# predkosciomierz.net
KiCad netlist of a schematic drawn in EAGLE
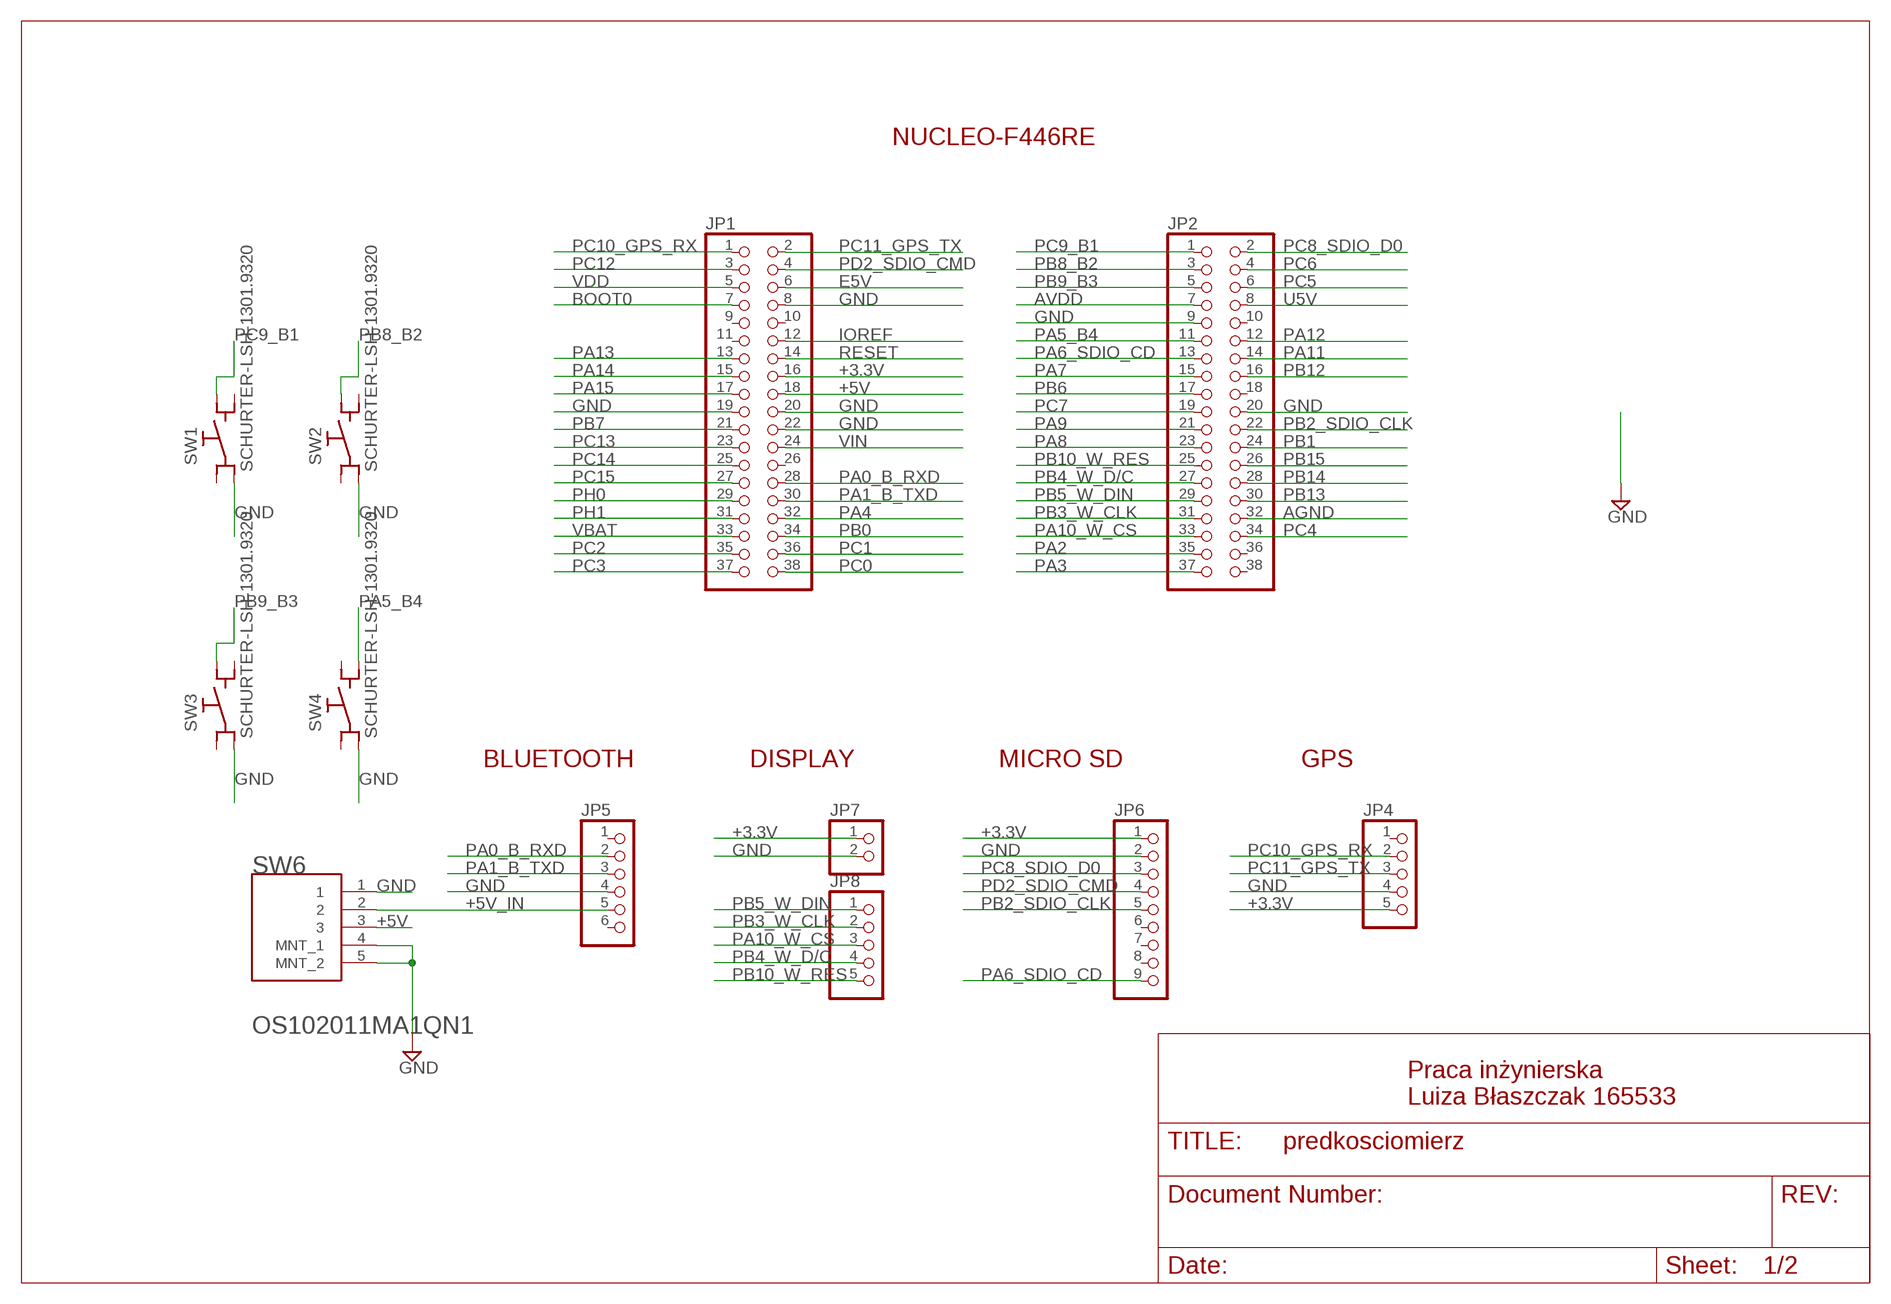
[diagram p0: schematic, sheet 1]
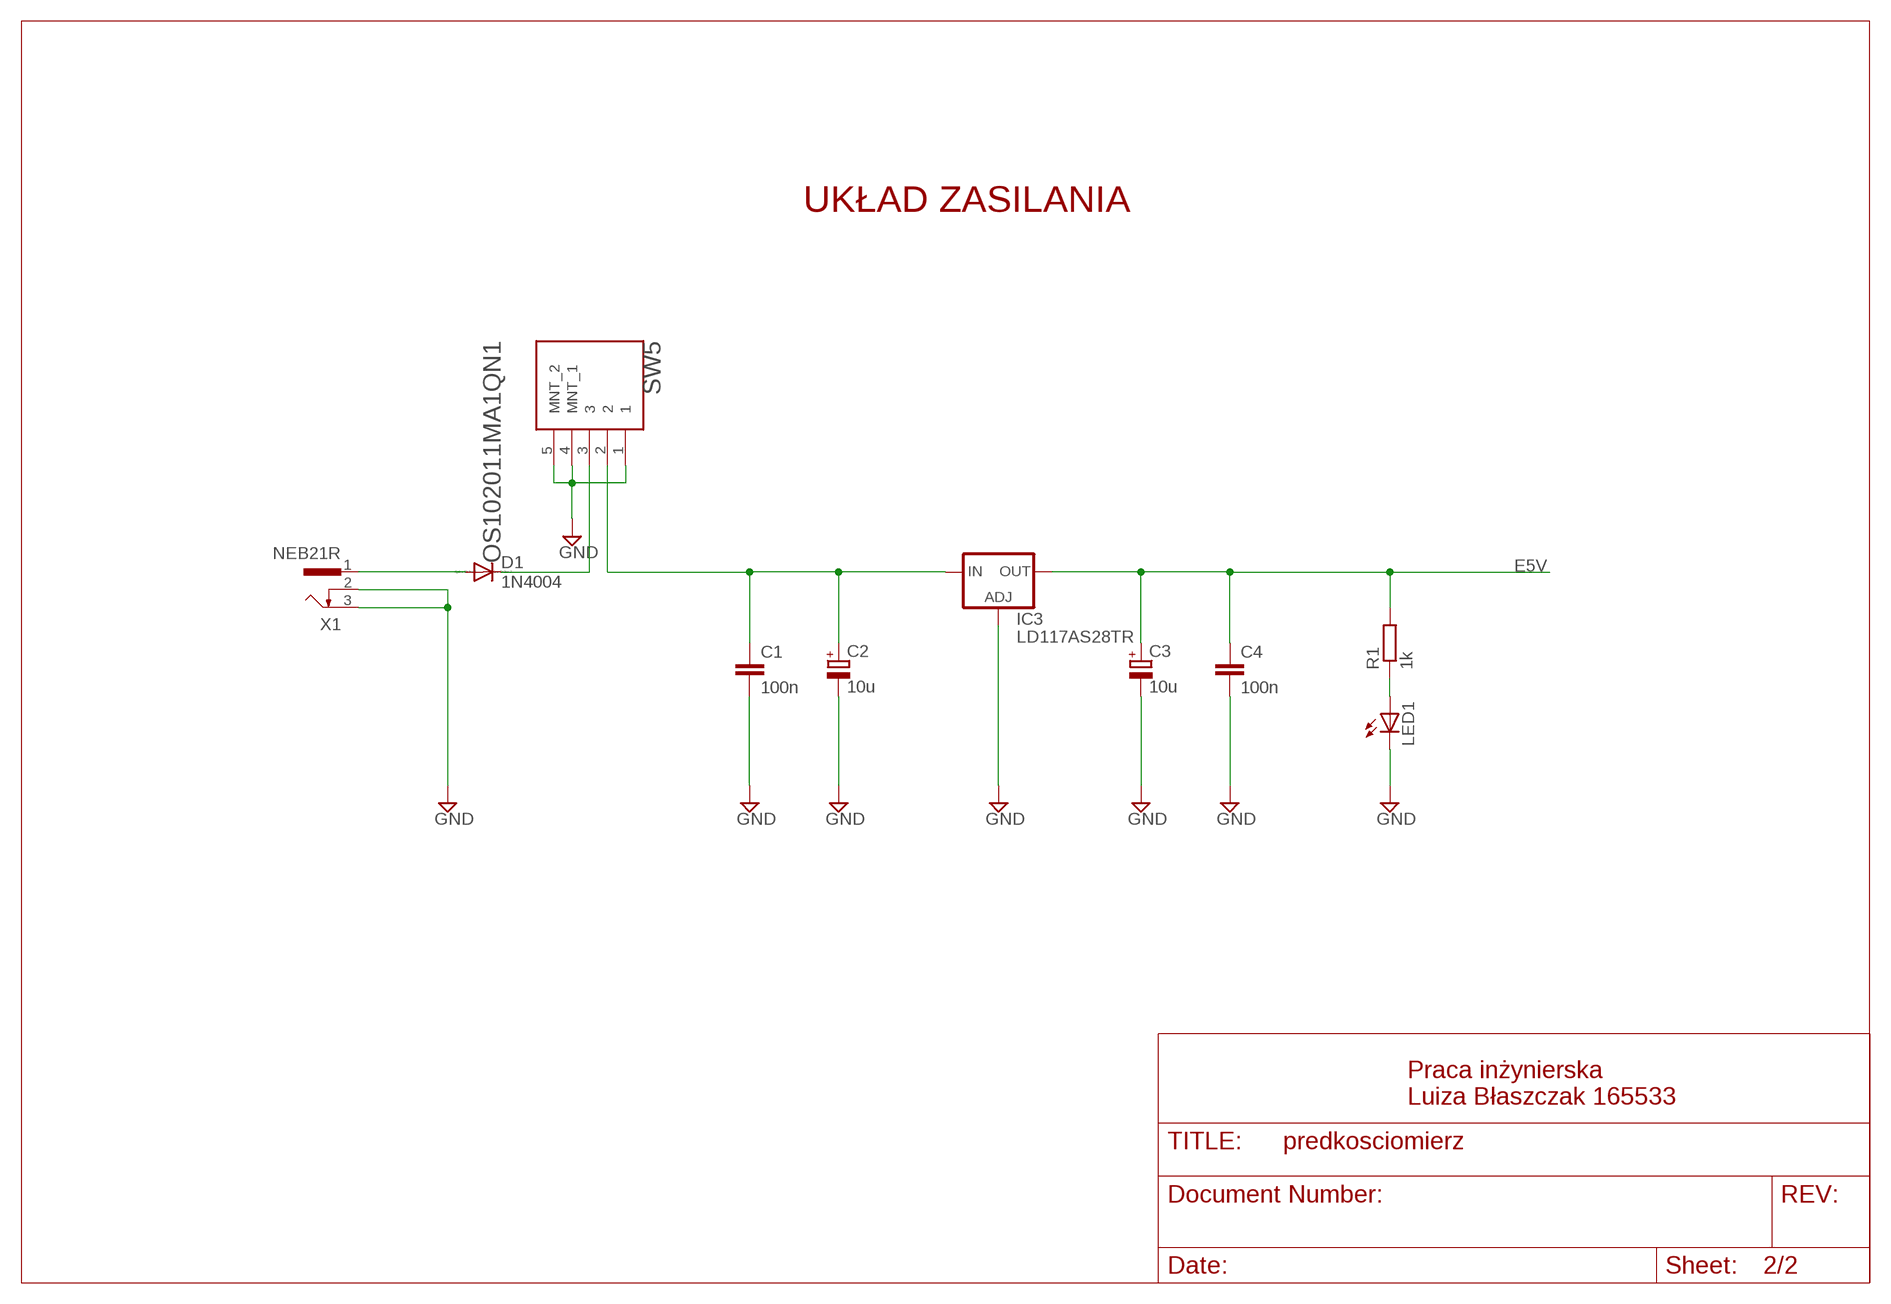
[diagram p1: schematic, sheet 2]

(export (version "E")
  (design (tool "Eeschema 10.0.6"))
  (components
    (comp (ref "JP1")
      (value "PINHD-2X19")
      (footprint "eagle-import:2X19")
      (libsource (lib "eagle-import") (part "PINHD-2X19"))
    )
    (comp (ref "JP2")
      (value "PINHD-2X19")
      (footprint "eagle-import:2X19")
      (libsource (lib "eagle-import") (part "PINHD-2X19"))
    )
    (comp (ref "JP4")
      (value "PINHD-1X5")
      (footprint "eagle-import:1X05")
      (libsource (lib "eagle-import") (part "PINHD-1X5"))
    )
    (comp (ref "JP5")
      (value "PINHD-1X6")
      (footprint "eagle-import:1X06")
      (libsource (lib "eagle-import") (part "PINHD-1X6"))
    )
    (comp (ref "JP6")
      (value "PINHD-1X9")
      (footprint "eagle-import:1X09")
      (libsource (lib "eagle-import") (part "PINHD-1X9"))
    )
    (comp (ref "JP7")
      (value "PINHD-1X2")
      (footprint "eagle-import:1X02")
      (libsource (lib "eagle-import") (part "PINHD-1X2"))
    )
    (comp (ref "JP8")
      (value "PINHD-1X5")
      (footprint "eagle-import:1X05")
      (libsource (lib "eagle-import") (part "PINHD-1X5"))
    )
    (comp (ref "SW1")
      (value "SCHURTER-LSH-1301.9320")
      (footprint "eagle-import:LSH")
      (libsource (lib "eagle-import") (part "SCHURTER-LSH-1301.9320"))
    )
    (comp (ref "SW2")
      (value "SCHURTER-LSH-1301.9320")
      (footprint "eagle-import:LSH")
      (libsource (lib "eagle-import") (part "SCHURTER-LSH-1301.9320"))
    )
    (comp (ref "SW3")
      (value "SCHURTER-LSH-1301.9320")
      (footprint "eagle-import:LSH")
      (libsource (lib "eagle-import") (part "SCHURTER-LSH-1301.9320"))
    )
    (comp (ref "SW4")
      (value "SCHURTER-LSH-1301.9320")
      (footprint "eagle-import:LSH")
      (libsource (lib "eagle-import") (part "SCHURTER-LSH-1301.9320"))
    )
    (comp (ref "SW6")
      (value "C&K_OS102011MA1QN1C&K_OS102011MA1QN1_0_0")
      (footprint "eagle-import:C&K_OS102011MA1QN1_0")
      (fields
        (field (name "DIGIKEY_PART_NUMBER") "CKN9559-ND")
        (field (name "MF") "C&K")
        (field (name "MOUSER_PART_NUMBER") "OS102011MA1QN1")
      )
      (libsource (lib "eagle-import") (part "C&K_OS102011MA1QN1C&K_OS102011MA1QN1_0_0"))
    )
    (comp (ref "C1")
      (value "100n")
      (footprint "eagle-import:C1210")
      (libsource (lib "eagle-import") (part "C-EUC1210"))
    )
    (comp (ref "C2")
      (value "10u")
      (footprint "eagle-import:E2-5")
      (libsource (lib "eagle-import") (part "CPOL-EUE2-5"))
    )
    (comp (ref "C3")
      (value "10u")
      (footprint "eagle-import:E2-5")
      (libsource (lib "eagle-import") (part "CPOL-EUE2-5"))
    )
    (comp (ref "C4")
      (value "100n")
      (footprint "eagle-import:C1210")
      (libsource (lib "eagle-import") (part "C-EUC1210"))
    )
    (comp (ref "D1")
      (value "1N4004")
      (footprint "eagle-import:DO41-10")
      (libsource (lib "eagle-import") (part "1N4004"))
    )
    (comp (ref "IC3")
      (value "LD117AS28TR")
      (footprint "eagle-import:SOT223")
      (libsource (lib "eagle-import") (part "LD117A?S28TR"))
    )
    (comp (ref "LED1")
      (value "LED5MM")
      (footprint "eagle-import:LED5MM")
      (libsource (lib "eagle-import") (part "LED5MM"))
    )
    (comp (ref "R1")
      (value "1k")
      (footprint "eagle-import:0204_7")
      (libsource (lib "eagle-import") (part "R-EU_0204/7"))
    )
    (comp (ref "SW5")
      (value "C&K_OS102011MA1QN1C&K_OS102011MA1QN1_0_0")
      (footprint "eagle-import:C&K_OS102011MA1QN1_0")
      (fields
        (field (name "DIGIKEY_PART_NUMBER") "CKN9559-ND")
        (field (name "MF") "C&K")
        (field (name "MOUSER_PART_NUMBER") "OS102011MA1QN1")
      )
      (libsource (lib "eagle-import") (part "C&K_OS102011MA1QN1C&K_OS102011MA1QN1_0_0"))
    )
    (comp (ref "X1")
      (value "NEB21R")
      (footprint "eagle-import:NEB21R")
      (fields (field (name "MPN") "NEB 21 R"))
      (libsource (lib "eagle-import") (part "NEB21R"))
    )
  )
  (nets
    (net (code "1") (name "+3.3V") (class "Default")
      (node (ref "JP1") (pin "16") (pinfunction "16_16") (pintype "passive"))
      (node (ref "JP4") (pin "5") (pinfunction "5_5") (pintype "passive"))
      (node (ref "JP6") (pin "1") (pinfunction "1_1") (pintype "passive"))
      (node (ref "JP7") (pin "1") (pinfunction "1_1") (pintype "passive"))
    )
    (net (code "2") (name "+5V") (class "Default")
      (node (ref "JP1") (pin "18") (pinfunction "18_18") (pintype "passive"))
      (node (ref "SW6") (pin "3") (pinfunction "3_3") (pintype "passive"))
    )
    (net (code "3") (name "+5V_IN") (class "Default")
      (node (ref "JP5") (pin "5") (pinfunction "5_5") (pintype "passive"))
      (node (ref "SW6") (pin "2") (pinfunction "2_2") (pintype "passive"))
    )
    (net (code "4") (name "AGND") (class "Default")
      (node (ref "JP2") (pin "32") (pinfunction "32_32") (pintype "passive"))
    )
    (net (code "5") (name "AVDD") (class "Default")
      (node (ref "JP2") (pin "7") (pinfunction "7_7") (pintype "passive"))
    )
    (net (code "6") (name "BOOT0") (class "Default")
      (node (ref "JP1") (pin "7") (pinfunction "7_7") (pintype "passive"))
    )
    (net (code "7") (name "E5V") (class "Default")
      (node (ref "C3") (pin "+") (pinfunction "+_+") (pintype "passive"))
      (node (ref "C4") (pin "1") (pinfunction "1_1") (pintype "passive"))
      (node (ref "IC3") (pin "4") (pinfunction "OUT_4") (pintype "passive"))
      (node (ref "JP1") (pin "6") (pinfunction "6_6") (pintype "passive"))
      (node (ref "R1") (pin "2") (pinfunction "2_2") (pintype "passive"))
    )
    (net (code "8") (name "GND") (class "Default")
      (node (ref "C1") (pin "2") (pinfunction "2_2") (pintype "passive"))
      (node (ref "C2") (pin "-") (pinfunction "-_-") (pintype "passive"))
      (node (ref "C3") (pin "-") (pinfunction "-_-") (pintype "passive"))
      (node (ref "C4") (pin "2") (pinfunction "2_2") (pintype "passive"))
      (node (ref "IC3") (pin "1") (pinfunction "ADJ_1") (pintype "input"))
      (node (ref "JP1") (pin "19") (pinfunction "19_19") (pintype "passive"))
      (node (ref "JP1") (pin "20") (pinfunction "20_20") (pintype "passive"))
      (node (ref "JP1") (pin "22") (pinfunction "22_22") (pintype "passive"))
      (node (ref "JP1") (pin "8") (pinfunction "8_8") (pintype "passive"))
      (node (ref "JP2") (pin "20") (pinfunction "20_20") (pintype "passive"))
      (node (ref "JP2") (pin "9") (pinfunction "9_9") (pintype "passive"))
      (node (ref "JP4") (pin "4") (pinfunction "4_4") (pintype "passive"))
      (node (ref "JP5") (pin "4") (pinfunction "4_4") (pintype "passive"))
      (node (ref "JP6") (pin "2") (pinfunction "2_2") (pintype "passive"))
      (node (ref "JP7") (pin "2") (pinfunction "2_2") (pintype "passive"))
      (node (ref "LED1") (pin "K") (pinfunction "C_K") (pintype "passive"))
      (node (ref "SW1") (pin "C2") (pinfunction "C_C2") (pintype "passive"))
      (node (ref "SW2") (pin "C2") (pinfunction "C_C2") (pintype "passive"))
      (node (ref "SW3") (pin "C2") (pinfunction "C_C2") (pintype "passive"))
      (node (ref "SW4") (pin "C2") (pinfunction "C_C2") (pintype "passive"))
      (node (ref "SW5") (pin "1") (pinfunction "1_1") (pintype "passive"))
      (node (ref "SW5") (pin "4") (pinfunction "MNT_1_4") (pintype "passive"))
      (node (ref "SW5") (pin "5") (pinfunction "MNT_2_5") (pintype "passive"))
      (node (ref "SW6") (pin "1") (pinfunction "1_1") (pintype "passive"))
      (node (ref "SW6") (pin "4") (pinfunction "MNT_1_4") (pintype "passive"))
      (node (ref "SW6") (pin "5") (pinfunction "MNT_2_5") (pintype "passive"))
      (node (ref "X1") (pin "2") (pinfunction "2_2") (pintype "passive"))
      (node (ref "X1") (pin "3") (pinfunction "3_3") (pintype "passive"))
    )
    (net (code "9") (name "IOREF") (class "Default")
      (node (ref "JP1") (pin "12") (pinfunction "12_12") (pintype "passive"))
    )
    (net (code "10") (name "Net-(D1-PadA)") (class "Default")
      (node (ref "D1") (pin "A") (pinfunction "A_A") (pintype "passive"))
      (node (ref "X1") (pin "1") (pinfunction "1_1") (pintype "passive"))
    )
    (net (code "11") (name "Net-(D1-PadC)") (class "Default")
      (node (ref "D1") (pin "C") (pinfunction "C_C") (pintype "passive"))
      (node (ref "SW5") (pin "3") (pinfunction "3_3") (pintype "passive"))
    )
    (net (code "12") (name "Net-(IC3-IN)") (class "Default")
      (node (ref "C1") (pin "1") (pinfunction "1_1") (pintype "passive"))
      (node (ref "C2") (pin "+") (pinfunction "+_+") (pintype "passive"))
      (node (ref "IC3") (pin "3") (pinfunction "IN_3") (pintype "input"))
      (node (ref "SW5") (pin "2") (pinfunction "2_2") (pintype "passive"))
    )
    (net (code "13") (name "Net-(LED1-PadA)") (class "Default")
      (node (ref "LED1") (pin "A") (pinfunction "A_A") (pintype "passive"))
      (node (ref "R1") (pin "1") (pinfunction "1_1") (pintype "passive"))
    )
    (net (code "14") (name "PA0_B_RXD") (class "Default")
      (node (ref "JP1") (pin "28") (pinfunction "28_28") (pintype "passive"))
      (node (ref "JP5") (pin "2") (pinfunction "2_2") (pintype "passive"))
    )
    (net (code "15") (name "PA1_B_TXD") (class "Default")
      (node (ref "JP1") (pin "30") (pinfunction "30_30") (pintype "passive"))
      (node (ref "JP5") (pin "3") (pinfunction "3_3") (pintype "passive"))
    )
    (net (code "16") (name "PA2") (class "Default")
      (node (ref "JP2") (pin "35") (pinfunction "35_35") (pintype "passive"))
    )
    (net (code "17") (name "PA3") (class "Default")
      (node (ref "JP2") (pin "37") (pinfunction "37_37") (pintype "passive"))
    )
    (net (code "18") (name "PA4") (class "Default")
      (node (ref "JP1") (pin "32") (pinfunction "32_32") (pintype "passive"))
    )
    (net (code "19") (name "PA5_B4") (class "Default")
      (node (ref "JP2") (pin "11") (pinfunction "11_11") (pintype "passive"))
      (node (ref "SW4") (pin "NO2") (pinfunction "NO_NO2") (pintype "passive"))
    )
    (net (code "20") (name "PA6_SDIO_CD") (class "Default")
      (node (ref "JP2") (pin "13") (pinfunction "13_13") (pintype "passive"))
      (node (ref "JP6") (pin "9") (pinfunction "9_9") (pintype "passive"))
    )
    (net (code "21") (name "PA7") (class "Default")
      (node (ref "JP2") (pin "15") (pinfunction "15_15") (pintype "passive"))
    )
    (net (code "22") (name "PA8") (class "Default")
      (node (ref "JP2") (pin "23") (pinfunction "23_23") (pintype "passive"))
    )
    (net (code "23") (name "PA9") (class "Default")
      (node (ref "JP2") (pin "21") (pinfunction "21_21") (pintype "passive"))
    )
    (net (code "24") (name "PA10_W_CS") (class "Default")
      (node (ref "JP2") (pin "33") (pinfunction "33_33") (pintype "passive"))
      (node (ref "JP8") (pin "3") (pinfunction "3_3") (pintype "passive"))
    )
    (net (code "25") (name "PA11") (class "Default")
      (node (ref "JP2") (pin "14") (pinfunction "14_14") (pintype "passive"))
    )
    (net (code "26") (name "PA12") (class "Default")
      (node (ref "JP2") (pin "12") (pinfunction "12_12") (pintype "passive"))
    )
    (net (code "27") (name "PA13") (class "Default")
      (node (ref "JP1") (pin "13") (pinfunction "13_13") (pintype "passive"))
    )
    (net (code "28") (name "PA14") (class "Default")
      (node (ref "JP1") (pin "15") (pinfunction "15_15") (pintype "passive"))
    )
    (net (code "29") (name "PA15") (class "Default")
      (node (ref "JP1") (pin "17") (pinfunction "17_17") (pintype "passive"))
    )
    (net (code "30") (name "PB0") (class "Default")
      (node (ref "JP1") (pin "34") (pinfunction "34_34") (pintype "passive"))
    )
    (net (code "31") (name "PB1") (class "Default")
      (node (ref "JP2") (pin "24") (pinfunction "24_24") (pintype "passive"))
    )
    (net (code "32") (name "PB2_SDIO_CLK") (class "Default")
      (node (ref "JP2") (pin "22") (pinfunction "22_22") (pintype "passive"))
      (node (ref "JP6") (pin "5") (pinfunction "5_5") (pintype "passive"))
    )
    (net (code "33") (name "PB3_W_CLK") (class "Default")
      (node (ref "JP2") (pin "31") (pinfunction "31_31") (pintype "passive"))
      (node (ref "JP8") (pin "2") (pinfunction "2_2") (pintype "passive"))
    )
    (net (code "34") (name "PB4_W_D{slash}C") (class "Default")
      (node (ref "JP2") (pin "27") (pinfunction "27_27") (pintype "passive"))
      (node (ref "JP8") (pin "4") (pinfunction "4_4") (pintype "passive"))
    )
    (net (code "35") (name "PB5_W_DIN") (class "Default")
      (node (ref "JP2") (pin "29") (pinfunction "29_29") (pintype "passive"))
      (node (ref "JP8") (pin "1") (pinfunction "1_1") (pintype "passive"))
    )
    (net (code "36") (name "PB6") (class "Default")
      (node (ref "JP2") (pin "17") (pinfunction "17_17") (pintype "passive"))
    )
    (net (code "37") (name "PB7") (class "Default")
      (node (ref "JP1") (pin "21") (pinfunction "21_21") (pintype "passive"))
    )
    (net (code "38") (name "PB8_B2") (class "Default")
      (node (ref "JP2") (pin "3") (pinfunction "3_3") (pintype "passive"))
      (node (ref "SW2") (pin "NO1") (pinfunction "NO_NO1") (pintype "passive"))
    )
    (net (code "39") (name "PB9_B3") (class "Default")
      (node (ref "JP2") (pin "5") (pinfunction "5_5") (pintype "passive"))
      (node (ref "SW3") (pin "NO1") (pinfunction "NO_NO1") (pintype "passive"))
    )
    (net (code "40") (name "PB10_W_RES") (class "Default")
      (node (ref "JP2") (pin "25") (pinfunction "25_25") (pintype "passive"))
      (node (ref "JP8") (pin "5") (pinfunction "5_5") (pintype "passive"))
    )
    (net (code "41") (name "PB12") (class "Default")
      (node (ref "JP2") (pin "16") (pinfunction "16_16") (pintype "passive"))
    )
    (net (code "42") (name "PB13") (class "Default")
      (node (ref "JP2") (pin "30") (pinfunction "30_30") (pintype "passive"))
    )
    (net (code "43") (name "PB14") (class "Default")
      (node (ref "JP2") (pin "28") (pinfunction "28_28") (pintype "passive"))
    )
    (net (code "44") (name "PB15") (class "Default")
      (node (ref "JP2") (pin "26") (pinfunction "26_26") (pintype "passive"))
    )
    (net (code "45") (name "PC0") (class "Default")
      (node (ref "JP1") (pin "38") (pinfunction "38_38") (pintype "passive"))
    )
    (net (code "46") (name "PC1") (class "Default")
      (node (ref "JP1") (pin "36") (pinfunction "36_36") (pintype "passive"))
    )
    (net (code "47") (name "PC2") (class "Default")
      (node (ref "JP1") (pin "35") (pinfunction "35_35") (pintype "passive"))
    )
    (net (code "48") (name "PC3") (class "Default")
      (node (ref "JP1") (pin "37") (pinfunction "37_37") (pintype "passive"))
    )
    (net (code "49") (name "PC4") (class "Default")
      (node (ref "JP2") (pin "34") (pinfunction "34_34") (pintype "passive"))
    )
    (net (code "50") (name "PC5") (class "Default")
      (node (ref "JP2") (pin "6") (pinfunction "6_6") (pintype "passive"))
    )
    (net (code "51") (name "PC6") (class "Default")
      (node (ref "JP2") (pin "4") (pinfunction "4_4") (pintype "passive"))
    )
    (net (code "52") (name "PC7") (class "Default")
      (node (ref "JP2") (pin "19") (pinfunction "19_19") (pintype "passive"))
    )
    (net (code "53") (name "PC8_SDIO_D0") (class "Default")
      (node (ref "JP2") (pin "2") (pinfunction "2_2") (pintype "passive"))
      (node (ref "JP6") (pin "3") (pinfunction "3_3") (pintype "passive"))
    )
    (net (code "54") (name "PC9_B1") (class "Default")
      (node (ref "JP2") (pin "1") (pinfunction "1_1") (pintype "passive"))
      (node (ref "SW1") (pin "NO1") (pinfunction "NO_NO1") (pintype "passive"))
    )
    (net (code "55") (name "PC10_GPS_RX") (class "Default")
      (node (ref "JP1") (pin "1") (pinfunction "1_1") (pintype "passive"))
      (node (ref "JP4") (pin "2") (pinfunction "2_2") (pintype "passive"))
    )
    (net (code "56") (name "PC11_GPS_TX") (class "Default")
      (node (ref "JP1") (pin "2") (pinfunction "2_2") (pintype "passive"))
      (node (ref "JP4") (pin "3") (pinfunction "3_3") (pintype "passive"))
    )
    (net (code "57") (name "PC12") (class "Default")
      (node (ref "JP1") (pin "3") (pinfunction "3_3") (pintype "passive"))
    )
    (net (code "58") (name "PC13") (class "Default")
      (node (ref "JP1") (pin "23") (pinfunction "23_23") (pintype "passive"))
    )
    (net (code "59") (name "PC14") (class "Default")
      (node (ref "JP1") (pin "25") (pinfunction "25_25") (pintype "passive"))
    )
    (net (code "60") (name "PC15") (class "Default")
      (node (ref "JP1") (pin "27") (pinfunction "27_27") (pintype "passive"))
    )
    (net (code "61") (name "PD2_SDIO_CMD") (class "Default")
      (node (ref "JP1") (pin "4") (pinfunction "4_4") (pintype "passive"))
      (node (ref "JP6") (pin "4") (pinfunction "4_4") (pintype "passive"))
    )
    (net (code "62") (name "PH0") (class "Default")
      (node (ref "JP1") (pin "29") (pinfunction "29_29") (pintype "passive"))
    )
    (net (code "63") (name "PH1") (class "Default")
      (node (ref "JP1") (pin "31") (pinfunction "31_31") (pintype "passive"))
    )
    (net (code "64") (name "RESET") (class "Default")
      (node (ref "JP1") (pin "14") (pinfunction "14_14") (pintype "passive"))
    )
    (net (code "65") (name "U5V") (class "Default")
      (node (ref "JP2") (pin "8") (pinfunction "8_8") (pintype "passive"))
    )
    (net (code "66") (name "VBAT") (class "Default")
      (node (ref "JP1") (pin "33") (pinfunction "33_33") (pintype "passive"))
    )
    (net (code "67") (name "VDD") (class "Default")
      (node (ref "JP1") (pin "5") (pinfunction "5_5") (pintype "passive"))
    )
    (net (code "68") (name "VIN") (class "Default")
      (node (ref "JP1") (pin "24") (pinfunction "24_24") (pintype "passive"))
    )
    (net (code "69") (name "unconnected-(JP1-Pad9)") (class "Default")
      (node (ref "JP1") (pin "9") (pinfunction "9_9") (pintype "passive"))
    )
    (net (code "70") (name "unconnected-(JP1-Pad10)") (class "Default")
      (node (ref "JP1") (pin "10") (pinfunction "10_10") (pintype "passive"))
    )
    (net (code "71") (name "unconnected-(JP1-Pad11)") (class "Default")
      (node (ref "JP1") (pin "11") (pinfunction "11_11") (pintype "passive"))
    )
    (net (code "72") (name "unconnected-(JP1-Pad26)") (class "Default")
      (node (ref "JP1") (pin "26") (pinfunction "26_26") (pintype "passive"))
    )
    (net (code "73") (name "unconnected-(JP2-Pad10)") (class "Default")
      (node (ref "JP2") (pin "10") (pinfunction "10_10") (pintype "passive"))
    )
    (net (code "74") (name "unconnected-(JP2-Pad18)") (class "Default")
      (node (ref "JP2") (pin "18") (pinfunction "18_18") (pintype "passive"))
    )
    (net (code "75") (name "unconnected-(JP2-Pad36)") (class "Default")
      (node (ref "JP2") (pin "36") (pinfunction "36_36") (pintype "passive"))
    )
    (net (code "76") (name "unconnected-(JP2-Pad38)") (class "Default")
      (node (ref "JP2") (pin "38") (pinfunction "38_38") (pintype "passive"))
    )
    (net (code "77") (name "unconnected-(JP4-Pad1)") (class "Default")
      (node (ref "JP4") (pin "1") (pinfunction "1_1") (pintype "passive"))
    )
    (net (code "78") (name "unconnected-(JP5-Pad1)") (class "Default")
      (node (ref "JP5") (pin "1") (pinfunction "1_1") (pintype "passive"))
    )
    (net (code "79") (name "unconnected-(JP5-Pad6)") (class "Default")
      (node (ref "JP5") (pin "6") (pinfunction "6_6") (pintype "passive"))
    )
    (net (code "80") (name "unconnected-(JP6-Pad6)") (class "Default")
      (node (ref "JP6") (pin "6") (pinfunction "6_6") (pintype "passive"))
    )
    (net (code "81") (name "unconnected-(JP6-Pad7)") (class "Default")
      (node (ref "JP6") (pin "7") (pinfunction "7_7") (pintype "passive"))
    )
    (net (code "82") (name "unconnected-(JP6-Pad8)") (class "Default")
      (node (ref "JP6") (pin "8") (pinfunction "8_8") (pintype "passive"))
    )
    (net (code "83") (name "unconnected-(SW1-C-PadC1)") (class "Default")
      (node (ref "SW1") (pin "C1") (pinfunction "C_C1") (pintype "passive"))
    )
    (net (code "84") (name "unconnected-(SW1-NO-PadNO2)") (class "Default")
      (node (ref "SW1") (pin "NO2") (pinfunction "NO_NO2") (pintype "passive"))
    )
    (net (code "85") (name "unconnected-(SW2-C-PadC1)") (class "Default")
      (node (ref "SW2") (pin "C1") (pinfunction "C_C1") (pintype "passive"))
    )
    (net (code "86") (name "unconnected-(SW2-NO-PadNO2)") (class "Default")
      (node (ref "SW2") (pin "NO2") (pinfunction "NO_NO2") (pintype "passive"))
    )
    (net (code "87") (name "unconnected-(SW3-C-PadC1)") (class "Default")
      (node (ref "SW3") (pin "C1") (pinfunction "C_C1") (pintype "passive"))
    )
    (net (code "88") (name "unconnected-(SW3-NO-PadNO2)") (class "Default")
      (node (ref "SW3") (pin "NO2") (pinfunction "NO_NO2") (pintype "passive"))
    )
    (net (code "89") (name "unconnected-(SW4-C-PadC1)") (class "Default")
      (node (ref "SW4") (pin "C1") (pinfunction "C_C1") (pintype "passive"))
    )
    (net (code "90") (name "unconnected-(SW4-NO-PadNO1)") (class "Default")
      (node (ref "SW4") (pin "NO1") (pinfunction "NO_NO1") (pintype "passive"))
    )
  )
)
